# MicroMod_STM32_Processor.net
KiCad netlist of a schematic drawn in EAGLE
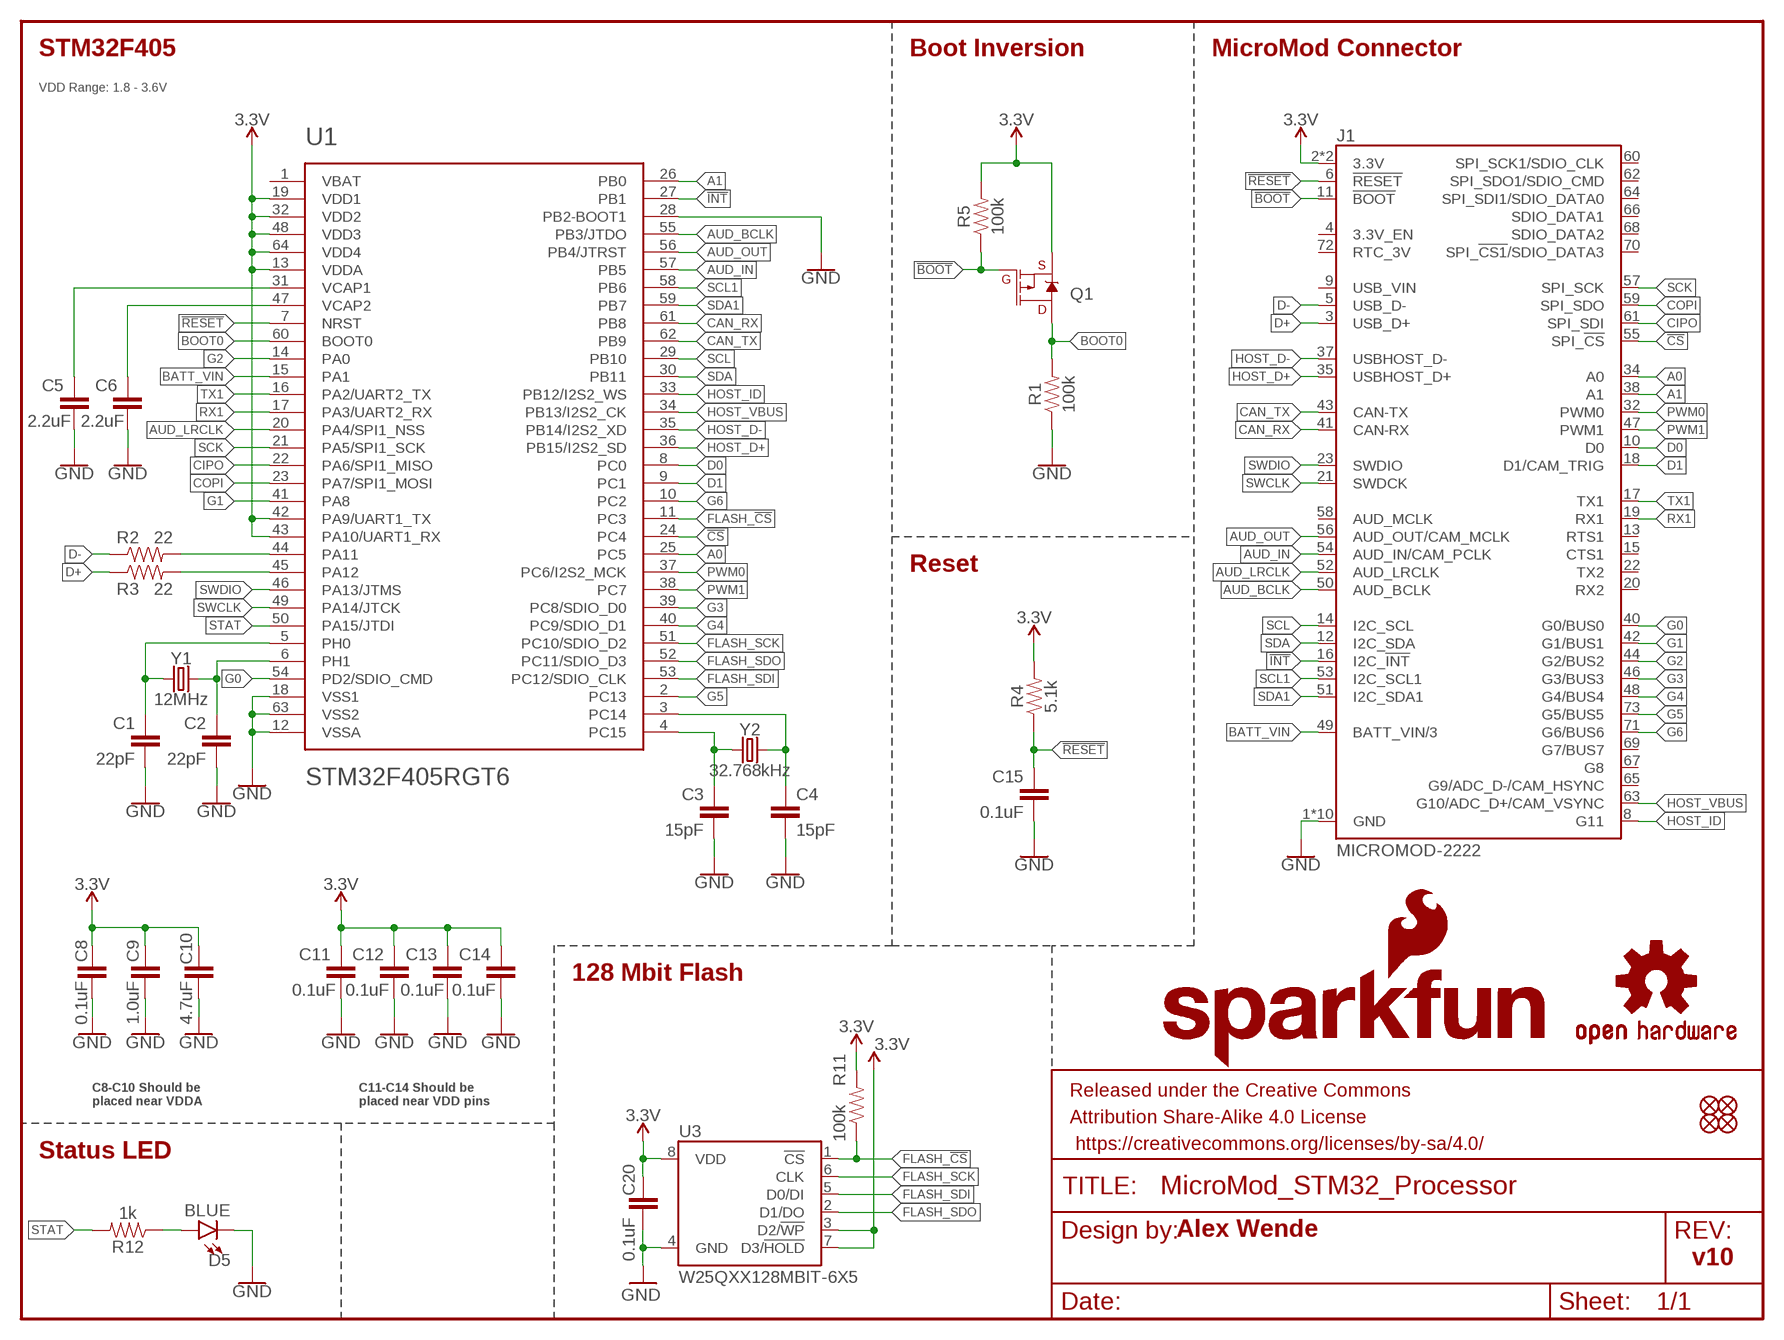
[diagram p0: schematic, sheet 1]

(export (version "E")
  (design (tool "Eeschema 10.0.6"))
  (components
    (comp (ref "C1")
      (value "22pF")
      (footprint "eagle-import:0402-TIGHT")
      (libsource (lib "eagle-import") (part "22PF-0402T-16V-10%"))
    )
    (comp (ref "C2")
      (value "22pF")
      (footprint "eagle-import:0402-TIGHT")
      (libsource (lib "eagle-import") (part "22PF-0402T-16V-10%"))
    )
    (comp (ref "C3")
      (value "15pF")
      (footprint "eagle-import:0402-TIGHT")
      (libsource (lib "eagle-import") (part "15PF-0402T-50V-5%"))
    )
    (comp (ref "C4")
      (value "15pF")
      (footprint "eagle-import:0402-TIGHT")
      (libsource (lib "eagle-import") (part "15PF-0402T-50V-5%"))
    )
    (comp (ref "C5")
      (value "2.2uF")
      (footprint "eagle-import:0402-TIGHT")
      (libsource (lib "eagle-import") (part "2.2UF-0402_TIGHT-10V-10%-X5R"))
    )
    (comp (ref "C6")
      (value "2.2uF")
      (footprint "eagle-import:0402-TIGHT")
      (libsource (lib "eagle-import") (part "2.2UF-0402_TIGHT-10V-10%-X5R"))
    )
    (comp (ref "C8")
      (value "0.1uF")
      (footprint "eagle-import:0402-TIGHT")
      (fields (field (name "SPICEPREFIX") "C"))
      (libsource (lib "eagle-import") (part "0.1UF-0402T-10V-10%-X7R"))
    )
    (comp (ref "C9")
      (value "1.0uF")
      (footprint "eagle-import:0402-TIGHT")
      (fields (field (name "SPICEPREFIX") "C"))
      (libsource (lib "eagle-import") (part "1.0UF-0402T-16V-10%"))
    )
    (comp (ref "C10")
      (value "4.7uF")
      (footprint "eagle-import:0402-TIGHT")
      (fields (field (name "SPICEPREFIX") "C"))
      (libsource (lib "eagle-import") (part "4.7UF-0402_TIGHT-6.3V-20%-X5R"))
    )
    (comp (ref "C11")
      (value "0.1uF")
      (footprint "eagle-import:0402-TIGHT")
      (libsource (lib "eagle-import") (part "0.1UF-0402T-10V-10%-X7R"))
    )
    (comp (ref "C12")
      (value "0.1uF")
      (footprint "eagle-import:0402-TIGHT")
      (libsource (lib "eagle-import") (part "0.1UF-0402T-10V-10%-X7R"))
    )
    (comp (ref "C13")
      (value "0.1uF")
      (footprint "eagle-import:0402-TIGHT")
      (libsource (lib "eagle-import") (part "0.1UF-0402T-10V-10%-X7R"))
    )
    (comp (ref "C14")
      (value "0.1uF")
      (footprint "eagle-import:0402-TIGHT")
      (libsource (lib "eagle-import") (part "0.1UF-0402T-10V-10%-X7R"))
    )
    (comp (ref "C15")
      (value "0.1uF")
      (footprint "eagle-import:0402-TIGHT")
      (libsource (lib "eagle-import") (part "0.1UF-0402T-10V-10%-X7R"))
    )
    (comp (ref "C20")
      (value "0.1uF")
      (footprint "eagle-import:0402-TIGHT")
      (libsource (lib "eagle-import") (part "0.1UF-0402T-10V-10%-X7R"))
    )
    (comp (ref "D5")
      (value "BLUE")
      (footprint "eagle-import:LED-0603")
      (libsource (lib "eagle-import") (part "LED-BLUE0603"))
    )
    (comp (ref "FD1")
      (value "FIDUCIALUFIDUCIAL")
      (footprint "eagle-import:FIDUCIAL-MICRO")
      (libsource (lib "eagle-import") (part "FIDUCIALUFIDUCIAL"))
    )
    (comp (ref "FD2")
      (value "FIDUCIALUFIDUCIAL")
      (footprint "eagle-import:FIDUCIAL-MICRO")
      (libsource (lib "eagle-import") (part "FIDUCIALUFIDUCIAL"))
    )
    (comp (ref "FD3")
      (value "FIDUCIALUFIDUCIAL")
      (footprint "eagle-import:FIDUCIAL-MICRO")
      (libsource (lib "eagle-import") (part "FIDUCIALUFIDUCIAL"))
    )
    (comp (ref "FD4")
      (value "FIDUCIALUFIDUCIAL")
      (footprint "eagle-import:FIDUCIAL-MICRO")
      (libsource (lib "eagle-import") (part "FIDUCIALUFIDUCIAL"))
    )
    (comp (ref "FRAME1")
      (value "FRAME-LETTER")
      (footprint "eagle-import:CREATIVE_COMMONS")
      (libsource (lib "eagle-import") (part "FRAME-LETTER"))
    )
    (comp (ref "J1")
      (value "MICROMOD-2222")
      (footprint "eagle-import:M.2-CARD-E-22")
      (libsource (lib "eagle-import") (part "MICROMOD-2222"))
    )
    (comp (ref "LOGO2")
      (value "OSHW-LOGOS")
      (footprint "eagle-import:OSHW-LOGO-S")
      (libsource (lib "eagle-import") (part "OSHW-LOGOS"))
    )
    (comp (ref "LOGO3")
      (value "SFE_LOGO_NAME_FLAME.1_INCH")
      (footprint "eagle-import:SFE_LOGO_NAME_FLAME_.1")
      (libsource (lib "eagle-import") (part "SFE_LOGO_NAME_FLAME.1_INCH"))
    )
    (comp (ref "Q1")
      (value "MOSFET_PCH-DMG2305UX-7")
      (footprint "eagle-import:SOT23-3")
      (libsource (lib "eagle-import") (part "MOSFET_PCH-DMG2305UX-7"))
    )
    (comp (ref "R1")
      (value "100k")
      (footprint "eagle-import:0402-TIGHT")
      (libsource (lib "eagle-import") (part "100KOHM-0402T-1/16W-1%"))
    )
    (comp (ref "R2")
      (value "22")
      (footprint "eagle-import:0402-TIGHT")
      (libsource (lib "eagle-import") (part "22OHM-0402T-1/16W-1%"))
    )
    (comp (ref "R3")
      (value "22")
      (footprint "eagle-import:0402-TIGHT")
      (libsource (lib "eagle-import") (part "22OHM-0402T-1/16W-1%"))
    )
    (comp (ref "R4")
      (value "5.1k")
      (footprint "eagle-import:0402-TIGHT")
      (libsource (lib "eagle-import") (part "5.1KOHM-0402T-1/16W-1%"))
    )
    (comp (ref "R5")
      (value "100k")
      (footprint "eagle-import:0402-TIGHT")
      (libsource (lib "eagle-import") (part "100KOHM-0402T-1/16W-1%"))
    )
    (comp (ref "R11")
      (value "100k")
      (footprint "eagle-import:0402-TIGHT")
      (libsource (lib "eagle-import") (part "100KOHM-0402T-1/16W-1%"))
    )
    (comp (ref "R12")
      (value "1k")
      (footprint "eagle-import:0402-TIGHT")
      (libsource (lib "eagle-import") (part "1KOHM-0402T-1/16W-1%"))
    )
    (comp (ref "U1")
      (value "STM32F405RGT6")
      (footprint "eagle-import:TQFP64")
      (libsource (lib "eagle-import") (part "STM32F405RG"))
    )
    (comp (ref "U3")
      (value "W25QXX128MBIT-6X5")
      (footprint "eagle-import:WSON-8-6X5")
      (libsource (lib "eagle-import") (part "W25QXX128MBIT-6X5"))
    )
    (comp (ref "Y1")
      (value "12MHz")
      (footprint "eagle-import:CRYSTAL-SMD-5X3.2-4PAD")
      (libsource (lib "eagle-import") (part "CRYSTAL-12MHZ{dblquote}"))
    )
    (comp (ref "Y2")
      (value "32.768kHz")
      (footprint "eagle-import:CRYSTAL-SMD-3.2X1.5MM")
      (libsource (lib "eagle-import") (part "CRYSTAL-32.768KHZSMD-3.2X1.5"))
    )
  )
  (nets
    (net (code "1") (name "/FLASH_~{CS}") (class "Default")
      (node (ref "R11") (pin "1") (pinfunction "1_1") (pintype "passive"))
      (node (ref "U1") (pin "11") (pinfunction "PC3_11") (pintype "bidirectional"))
      (node (ref "U3") (pin "1") (pinfunction "~{CS}_1") (pintype "bidirectional"))
    )
    (net (code "2") (name "/~{BOOT}") (class "Default")
      (node (ref "J1") (pin "11") (pinfunction "~{BOOT}_11") (pintype "bidirectional"))
      (node (ref "Q1") (pin "1") (pinfunction "G_1") (pintype "bidirectional"))
      (node (ref "R5") (pin "1") (pinfunction "1_1") (pintype "passive"))
    )
    (net (code "3") (name "/~{CS}") (class "Default")
      (node (ref "J1") (pin "55") (pinfunction "SPI_~{CS}_55") (pintype "bidirectional"))
      (node (ref "U1") (pin "24") (pinfunction "PC4_24") (pintype "bidirectional"))
    )
    (net (code "4") (name "/~{INT}") (class "Default")
      (node (ref "J1") (pin "16") (pinfunction "I2C_~{INT}_16") (pintype "bidirectional"))
      (node (ref "U1") (pin "27") (pinfunction "PB1_27") (pintype "bidirectional"))
    )
    (net (code "5") (name "/~{RESET}") (class "Default")
      (node (ref "C15") (pin "1") (pinfunction "1_1") (pintype "passive"))
      (node (ref "J1") (pin "6") (pinfunction "~{RESET}_6") (pintype "bidirectional"))
      (node (ref "R4") (pin "1") (pinfunction "1_1") (pintype "passive"))
      (node (ref "U1") (pin "7") (pinfunction "NRST_7") (pintype "bidirectional"))
    )
    (net (code "6") (name "3.3V") (class "Default")
      (node (ref "C10") (pin "1") (pinfunction "1_1") (pintype "passive"))
      (node (ref "C11") (pin "1") (pinfunction "1_1") (pintype "passive"))
      (node (ref "C12") (pin "1") (pinfunction "1_1") (pintype "passive"))
      (node (ref "C13") (pin "1") (pinfunction "1_1") (pintype "passive"))
      (node (ref "C14") (pin "1") (pinfunction "1_1") (pintype "passive"))
      (node (ref "C20") (pin "1") (pinfunction "1_1") (pintype "passive"))
      (node (ref "C8") (pin "1") (pinfunction "1_1") (pintype "passive"))
      (node (ref "C9") (pin "1") (pinfunction "1_1") (pintype "passive"))
      (node (ref "J1") (pin "2") (pinfunction "3.3V_2") (pintype "bidirectional"))
      (node (ref "J1") (pin "74") (pinfunction "3.3V_74") (pintype "bidirectional"))
      (node (ref "Q1") (pin "2") (pinfunction "S_2") (pintype "bidirectional"))
      (node (ref "R11") (pin "2") (pinfunction "2_2") (pintype "passive"))
      (node (ref "R4") (pin "2") (pinfunction "2_2") (pintype "passive"))
      (node (ref "R5") (pin "2") (pinfunction "2_2") (pintype "passive"))
      (node (ref "U1") (pin "13") (pinfunction "VDDA_13") (pintype "bidirectional"))
      (node (ref "U1") (pin "19") (pinfunction "VDD1_19") (pintype "bidirectional"))
      (node (ref "U1") (pin "32") (pinfunction "VDD2_32") (pintype "bidirectional"))
      (node (ref "U1") (pin "42") (pinfunction "PA9/UART1_TX_42") (pintype "bidirectional"))
      (node (ref "U1") (pin "43") (pinfunction "PA10/UART1_RX_43") (pintype "bidirectional"))
      (node (ref "U1") (pin "48") (pinfunction "VDD3_48") (pintype "bidirectional"))
      (node (ref "U1") (pin "64") (pinfunction "VDD4_64") (pintype "bidirectional"))
      (node (ref "U3") (pin "3") (pinfunction "D2/~{WP}_3") (pintype "bidirectional"))
      (node (ref "U3") (pin "7") (pinfunction "D3/~{HOLD}_7") (pintype "bidirectional"))
      (node (ref "U3") (pin "8") (pinfunction "VDD_8") (pintype "bidirectional"))
    )
    (net (code "7") (name "A0") (class "Default")
      (node (ref "J1") (pin "34") (pinfunction "A0_34") (pintype "bidirectional"))
      (node (ref "U1") (pin "25") (pinfunction "PC5_25") (pintype "bidirectional"))
    )
    (net (code "8") (name "A1") (class "Default")
      (node (ref "J1") (pin "38") (pinfunction "A1_38") (pintype "bidirectional"))
      (node (ref "U1") (pin "26") (pinfunction "PB0_26") (pintype "bidirectional"))
    )
    (net (code "9") (name "AUD_BCLK") (class "Default")
      (node (ref "J1") (pin "50") (pinfunction "AUD_BCLK_50") (pintype "bidirectional"))
      (node (ref "U1") (pin "55") (pinfunction "PB3/JTDO_55") (pintype "bidirectional"))
    )
    (net (code "10") (name "AUD_IN") (class "Default")
      (node (ref "J1") (pin "54") (pinfunction "AUD_IN/CAM_PCLK_54") (pintype "bidirectional"))
      (node (ref "U1") (pin "57") (pinfunction "PB5_57") (pintype "bidirectional"))
    )
    (net (code "11") (name "AUD_LRCLK") (class "Default")
      (node (ref "J1") (pin "52") (pinfunction "AUD_LRCLK_52") (pintype "bidirectional"))
      (node (ref "U1") (pin "20") (pinfunction "PA4/SPI1_NSS_20") (pintype "bidirectional"))
    )
    (net (code "12") (name "AUD_OUT") (class "Default")
      (node (ref "J1") (pin "56") (pinfunction "AUD_OUT/CAM_MCLK_56") (pintype "bidirectional"))
      (node (ref "U1") (pin "56") (pinfunction "PB4/JTRST_56") (pintype "bidirectional"))
    )
    (net (code "13") (name "BATT_VIN") (class "Default")
      (node (ref "J1") (pin "49") (pinfunction "BATT_VIN/3_49") (pintype "bidirectional"))
      (node (ref "U1") (pin "15") (pinfunction "PA1_15") (pintype "bidirectional"))
    )
    (net (code "14") (name "BOOT0") (class "Default")
      (node (ref "Q1") (pin "3") (pinfunction "D_3") (pintype "bidirectional"))
      (node (ref "R1") (pin "2") (pinfunction "2_2") (pintype "passive"))
      (node (ref "U1") (pin "60") (pinfunction "BOOT0_60") (pintype "bidirectional"))
    )
    (net (code "15") (name "CAN_RX") (class "Default")
      (node (ref "J1") (pin "41") (pinfunction "CAN-RX_41") (pintype "bidirectional"))
      (node (ref "U1") (pin "61") (pinfunction "PB8_61") (pintype "bidirectional"))
    )
    (net (code "16") (name "CAN_TX") (class "Default")
      (node (ref "J1") (pin "43") (pinfunction "CAN-TX_43") (pintype "bidirectional"))
      (node (ref "U1") (pin "62") (pinfunction "PB9_62") (pintype "bidirectional"))
    )
    (net (code "17") (name "CIPO") (class "Default")
      (node (ref "J1") (pin "61") (pinfunction "SPI_SDI_61") (pintype "bidirectional"))
      (node (ref "U1") (pin "22") (pinfunction "PA6/SPI1_MISO_22") (pintype "bidirectional"))
    )
    (net (code "18") (name "COPI") (class "Default")
      (node (ref "J1") (pin "59") (pinfunction "SPI_SDO_59") (pintype "bidirectional"))
      (node (ref "U1") (pin "23") (pinfunction "PA7/SPI1_MOSI_23") (pintype "bidirectional"))
    )
    (net (code "19") (name "D+") (class "Default")
      (node (ref "J1") (pin "3") (pinfunction "USB_D+_3") (pintype "bidirectional"))
      (node (ref "R3") (pin "1") (pinfunction "1_1") (pintype "passive"))
    )
    (net (code "20") (name "D-") (class "Default")
      (node (ref "J1") (pin "5") (pinfunction "USB_D-_5") (pintype "bidirectional"))
      (node (ref "R2") (pin "1") (pinfunction "1_1") (pintype "passive"))
    )
    (net (code "21") (name "D0") (class "Default")
      (node (ref "J1") (pin "10") (pinfunction "D0_10") (pintype "bidirectional"))
      (node (ref "U1") (pin "8") (pinfunction "PC0_8") (pintype "bidirectional"))
    )
    (net (code "22") (name "D1") (class "Default")
      (node (ref "J1") (pin "18") (pinfunction "D1/CAM_TRIG_18") (pintype "bidirectional"))
      (node (ref "U1") (pin "9") (pinfunction "PC1_9") (pintype "bidirectional"))
    )
    (net (code "23") (name "FLASH_SCK") (class "Default")
      (node (ref "U1") (pin "51") (pinfunction "PC10/SDIO_D2_51") (pintype "bidirectional"))
      (node (ref "U3") (pin "6") (pinfunction "CLK_6") (pintype "bidirectional"))
    )
    (net (code "24") (name "FLASH_SDI") (class "Default")
      (node (ref "U1") (pin "53") (pinfunction "PC12/SDIO_CLK_53") (pintype "bidirectional"))
      (node (ref "U3") (pin "5") (pinfunction "D0/DI_5") (pintype "bidirectional"))
    )
    (net (code "25") (name "FLASH_SDO") (class "Default")
      (node (ref "U1") (pin "52") (pinfunction "PC11/SDIO_D3_52") (pintype "bidirectional"))
      (node (ref "U3") (pin "2") (pinfunction "D1/DO_2") (pintype "bidirectional"))
    )
    (net (code "26") (name "G0") (class "Default")
      (node (ref "J1") (pin "40") (pinfunction "G0/BUS0_40") (pintype "bidirectional"))
      (node (ref "U1") (pin "54") (pinfunction "PD2/SDIO_CMD_54") (pintype "bidirectional"))
    )
    (net (code "27") (name "G1") (class "Default")
      (node (ref "J1") (pin "42") (pinfunction "G1/BUS1_42") (pintype "bidirectional"))
      (node (ref "U1") (pin "41") (pinfunction "PA8_41") (pintype "bidirectional"))
    )
    (net (code "28") (name "G2") (class "Default")
      (node (ref "J1") (pin "44") (pinfunction "G2/BUS2_44") (pintype "bidirectional"))
      (node (ref "U1") (pin "14") (pinfunction "PA0_14") (pintype "bidirectional"))
    )
    (net (code "29") (name "G3") (class "Default")
      (node (ref "J1") (pin "46") (pinfunction "G3/BUS3_46") (pintype "bidirectional"))
      (node (ref "U1") (pin "39") (pinfunction "PC8/SDIO_D0_39") (pintype "bidirectional"))
    )
    (net (code "30") (name "G4") (class "Default")
      (node (ref "J1") (pin "48") (pinfunction "G4/BUS4_48") (pintype "bidirectional"))
      (node (ref "U1") (pin "40") (pinfunction "PC9/SDIO_D1_40") (pintype "bidirectional"))
    )
    (net (code "31") (name "G5") (class "Default")
      (node (ref "J1") (pin "73") (pinfunction "G5/BUS5_73") (pintype "bidirectional"))
      (node (ref "U1") (pin "2") (pinfunction "PC13_2") (pintype "bidirectional"))
    )
    (net (code "32") (name "G6") (class "Default")
      (node (ref "J1") (pin "71") (pinfunction "G6/BUS6_71") (pintype "bidirectional"))
      (node (ref "U1") (pin "10") (pinfunction "PC2_10") (pintype "bidirectional"))
    )
    (net (code "33") (name "GND") (class "Default")
      (node (ref "C1") (pin "2") (pinfunction "2_2") (pintype "passive"))
      (node (ref "C10") (pin "2") (pinfunction "2_2") (pintype "passive"))
      (node (ref "C11") (pin "2") (pinfunction "2_2") (pintype "passive"))
      (node (ref "C12") (pin "2") (pinfunction "2_2") (pintype "passive"))
      (node (ref "C13") (pin "2") (pinfunction "2_2") (pintype "passive"))
      (node (ref "C14") (pin "2") (pinfunction "2_2") (pintype "passive"))
      (node (ref "C15") (pin "2") (pinfunction "2_2") (pintype "passive"))
      (node (ref "C2") (pin "2") (pinfunction "2_2") (pintype "passive"))
      (node (ref "C20") (pin "2") (pinfunction "2_2") (pintype "passive"))
      (node (ref "C3") (pin "2") (pinfunction "2_2") (pintype "passive"))
      (node (ref "C4") (pin "2") (pinfunction "2_2") (pintype "passive"))
      (node (ref "C5") (pin "2") (pinfunction "2_2") (pintype "passive"))
      (node (ref "C6") (pin "2") (pinfunction "2_2") (pintype "passive"))
      (node (ref "C8") (pin "2") (pinfunction "2_2") (pintype "passive"))
      (node (ref "C9") (pin "2") (pinfunction "2_2") (pintype "passive"))
      (node (ref "D5") (pin "C") (pinfunction "C_C") (pintype "passive"))
      (node (ref "J1") (pin "1") (pinfunction "GND_1") (pintype "bidirectional"))
      (node (ref "J1") (pin "33") (pinfunction "GND_33") (pintype "bidirectional"))
      (node (ref "J1") (pin "36") (pinfunction "GND_36") (pintype "bidirectional"))
      (node (ref "J1") (pin "39") (pinfunction "GND_39") (pintype "bidirectional"))
      (node (ref "J1") (pin "45") (pinfunction "GND_45") (pintype "bidirectional"))
      (node (ref "J1") (pin "7") (pinfunction "GND_7") (pintype "bidirectional"))
      (node (ref "J1") (pin "75") (pinfunction "GND_75") (pintype "bidirectional"))
      (node (ref "J1") (pin "GND1") (pinfunction "GND_GND1") (pintype "bidirectional"))
      (node (ref "J1") (pin "GND2") (pinfunction "GND_GND2") (pintype "bidirectional"))
      (node (ref "J1") (pin "GND3") (pinfunction "GND_GND3") (pintype "bidirectional"))
      (node (ref "R1") (pin "1") (pinfunction "1_1") (pintype "passive"))
      (node (ref "U1") (pin "12") (pinfunction "VSSA_12") (pintype "bidirectional"))
      (node (ref "U1") (pin "18") (pinfunction "VSS1_18") (pintype "bidirectional"))
      (node (ref "U1") (pin "28") (pinfunction "PB2-BOOT1_28") (pintype "bidirectional"))
      (node (ref "U1") (pin "63") (pinfunction "VSS2_63") (pintype "bidirectional"))
      (node (ref "U3") (pin "4") (pinfunction "GND_4") (pintype "bidirectional"))
    )
    (net (code "34") (name "HOST_D+") (class "Default")
      (node (ref "J1") (pin "35") (pinfunction "USBHOST_D+_35") (pintype "bidirectional"))
      (node (ref "U1") (pin "36") (pinfunction "PB15/I2S2_SD_36") (pintype "bidirectional"))
    )
    (net (code "35") (name "HOST_D-") (class "Default")
      (node (ref "J1") (pin "37") (pinfunction "USBHOST_D-_37") (pintype "bidirectional"))
      (node (ref "U1") (pin "35") (pinfunction "PB14/I2S2_XD_35") (pintype "bidirectional"))
    )
    (net (code "36") (name "HOST_ID") (class "Default")
      (node (ref "J1") (pin "8") (pinfunction "G11_8") (pintype "bidirectional"))
      (node (ref "U1") (pin "33") (pinfunction "PB12/I2S2_WS_33") (pintype "bidirectional"))
    )
    (net (code "37") (name "HOST_VBUS") (class "Default")
      (node (ref "J1") (pin "63") (pinfunction "G10/ADC_D+/CAM_VSYNC_63") (pintype "bidirectional"))
      (node (ref "U1") (pin "34") (pinfunction "PB13/I2S2_CK_34") (pintype "bidirectional"))
    )
    (net (code "38") (name "Net-(D5-PadA)") (class "Default")
      (node (ref "D5") (pin "A") (pinfunction "A_A") (pintype "passive"))
      (node (ref "R12") (pin "1") (pinfunction "1_1") (pintype "passive"))
    )
    (net (code "39") (name "Net-(U1-PA11)") (class "Default")
      (node (ref "R2") (pin "2") (pinfunction "2_2") (pintype "passive"))
      (node (ref "U1") (pin "44") (pinfunction "PA11_44") (pintype "bidirectional"))
    )
    (net (code "40") (name "Net-(U1-PA12)") (class "Default")
      (node (ref "R3") (pin "2") (pinfunction "2_2") (pintype "passive"))
      (node (ref "U1") (pin "45") (pinfunction "PA12_45") (pintype "bidirectional"))
    )
    (net (code "41") (name "Net-(U1-PC14)") (class "Default")
      (node (ref "C4") (pin "1") (pinfunction "1_1") (pintype "passive"))
      (node (ref "U1") (pin "3") (pinfunction "PC14_3") (pintype "bidirectional"))
      (node (ref "Y2") (pin "P$2") (pinfunction "2_P$2") (pintype "passive"))
    )
    (net (code "42") (name "Net-(U1-PC15)") (class "Default")
      (node (ref "C3") (pin "1") (pinfunction "1_1") (pintype "passive"))
      (node (ref "U1") (pin "4") (pinfunction "PC15_4") (pintype "bidirectional"))
      (node (ref "Y2") (pin "P$1") (pinfunction "1_P$1") (pintype "passive"))
    )
    (net (code "43") (name "Net-(U1-PH0)") (class "Default")
      (node (ref "C1") (pin "1") (pinfunction "1_1") (pintype "passive"))
      (node (ref "U1") (pin "5") (pinfunction "PH0_5") (pintype "bidirectional"))
      (node (ref "Y1") (pin "1") (pinfunction "1_1") (pintype "passive"))
    )
    (net (code "44") (name "Net-(U1-PH1)") (class "Default")
      (node (ref "C2") (pin "1") (pinfunction "1_1") (pintype "passive"))
      (node (ref "U1") (pin "6") (pinfunction "PH1_6") (pintype "bidirectional"))
      (node (ref "Y1") (pin "3") (pinfunction "2_3") (pintype "passive"))
    )
    (net (code "45") (name "Net-(U1-VCAP1)") (class "Default")
      (node (ref "C5") (pin "1") (pinfunction "1_1") (pintype "passive"))
      (node (ref "U1") (pin "31") (pinfunction "VCAP1_31") (pintype "bidirectional"))
    )
    (net (code "46") (name "Net-(U1-VCAP2)") (class "Default")
      (node (ref "C6") (pin "1") (pinfunction "1_1") (pintype "passive"))
      (node (ref "U1") (pin "47") (pinfunction "VCAP2_47") (pintype "bidirectional"))
    )
    (net (code "47") (name "PWM0") (class "Default")
      (node (ref "J1") (pin "32") (pinfunction "PWM0_32") (pintype "bidirectional"))
      (node (ref "U1") (pin "37") (pinfunction "PC6/I2S2_MCK_37") (pintype "bidirectional"))
    )
    (net (code "48") (name "PWM1") (class "Default")
      (node (ref "J1") (pin "47") (pinfunction "PWM1_47") (pintype "bidirectional"))
      (node (ref "U1") (pin "38") (pinfunction "PC7_38") (pintype "bidirectional"))
    )
    (net (code "49") (name "RX1") (class "Default")
      (node (ref "J1") (pin "19") (pinfunction "RX1_19") (pintype "bidirectional"))
      (node (ref "U1") (pin "17") (pinfunction "PA3/UART2_RX_17") (pintype "bidirectional"))
    )
    (net (code "50") (name "SCK") (class "Default")
      (node (ref "J1") (pin "57") (pinfunction "SPI_SCK_57") (pintype "bidirectional"))
      (node (ref "U1") (pin "21") (pinfunction "PA5/SPI1_SCK_21") (pintype "bidirectional"))
    )
    (net (code "51") (name "SCL") (class "Default")
      (node (ref "J1") (pin "14") (pinfunction "I2C_SCL_14") (pintype "bidirectional"))
      (node (ref "U1") (pin "29") (pinfunction "PB10_29") (pintype "bidirectional"))
    )
    (net (code "52") (name "SCL1") (class "Default")
      (node (ref "J1") (pin "53") (pinfunction "I2C_SCL1_53") (pintype "bidirectional"))
      (node (ref "U1") (pin "58") (pinfunction "PB6_58") (pintype "bidirectional"))
    )
    (net (code "53") (name "SDA") (class "Default")
      (node (ref "J1") (pin "12") (pinfunction "I2C_SDA_12") (pintype "bidirectional"))
      (node (ref "U1") (pin "30") (pinfunction "PB11_30") (pintype "bidirectional"))
    )
    (net (code "54") (name "SDA1") (class "Default")
      (node (ref "J1") (pin "51") (pinfunction "I2C_SDA1_51") (pintype "bidirectional"))
      (node (ref "U1") (pin "59") (pinfunction "PB7_59") (pintype "bidirectional"))
    )
    (net (code "55") (name "STAT") (class "Default")
      (node (ref "R12") (pin "2") (pinfunction "2_2") (pintype "passive"))
      (node (ref "U1") (pin "50") (pinfunction "PA15/JTDI_50") (pintype "bidirectional"))
    )
    (net (code "56") (name "SWCLK") (class "Default")
      (node (ref "J1") (pin "21") (pinfunction "SWDCK_21") (pintype "bidirectional"))
      (node (ref "U1") (pin "49") (pinfunction "PA14/JTCK_49") (pintype "bidirectional"))
    )
    (net (code "57") (name "SWDIO") (class "Default")
      (node (ref "J1") (pin "23") (pinfunction "SWDIO_23") (pintype "bidirectional"))
      (node (ref "U1") (pin "46") (pinfunction "PA13/JTMS_46") (pintype "bidirectional"))
    )
    (net (code "58") (name "TX1") (class "Default")
      (node (ref "J1") (pin "17") (pinfunction "TX1_17") (pintype "bidirectional"))
      (node (ref "U1") (pin "16") (pinfunction "PA2/UART2_TX_16") (pintype "bidirectional"))
    )
    (net (code "59") (name "unconnected-(J1-3.3V_EN-Pad4)") (class "Default")
      (node (ref "J1") (pin "4") (pinfunction "3.3V_EN_4") (pintype "bidirectional"))
    )
    (net (code "60") (name "unconnected-(J1-AUD_MCLK-Pad58)") (class "Default")
      (node (ref "J1") (pin "58") (pinfunction "AUD_MCLK_58") (pintype "bidirectional"))
    )
    (net (code "61") (name "unconnected-(J1-CTS1-Pad15)") (class "Default")
      (node (ref "J1") (pin "15") (pinfunction "CTS1_15") (pintype "bidirectional"))
    )
    (net (code "62") (name "unconnected-(J1-G7{slash}BUS7-Pad69)") (class "Default")
      (node (ref "J1") (pin "69") (pinfunction "G7/BUS7_69") (pintype "bidirectional"))
    )
    (net (code "63") (name "unconnected-(J1-G8-Pad67)") (class "Default")
      (node (ref "J1") (pin "67") (pinfunction "G8_67") (pintype "bidirectional"))
    )
    (net (code "64") (name "unconnected-(J1-G9{slash}ADC_D-{slash}CAM_HSYNC-Pad65)") (class "Default")
      (node (ref "J1") (pin "65") (pinfunction "G9/ADC_D-/CAM_HSYNC_65") (pintype "bidirectional"))
    )
    (net (code "65") (name "unconnected-(J1-RTC_3V-Pad72)") (class "Default")
      (node (ref "J1") (pin "72") (pinfunction "RTC_3V_72") (pintype "bidirectional"))
    )
    (net (code "66") (name "unconnected-(J1-RTS1-Pad13)") (class "Default")
      (node (ref "J1") (pin "13") (pinfunction "RTS1_13") (pintype "bidirectional"))
    )
    (net (code "67") (name "unconnected-(J1-RX2-Pad20)") (class "Default")
      (node (ref "J1") (pin "20") (pinfunction "RX2_20") (pintype "bidirectional"))
    )
    (net (code "68") (name "unconnected-(J1-SDIO_DATA1-Pad66)") (class "Default")
      (node (ref "J1") (pin "66") (pinfunction "SDIO_DATA1_66") (pintype "bidirectional"))
    )
    (net (code "69") (name "unconnected-(J1-SDIO_DATA2-Pad68)") (class "Default")
      (node (ref "J1") (pin "68") (pinfunction "SDIO_DATA2_68") (pintype "bidirectional"))
    )
    (net (code "70") (name "unconnected-(J1-SPI_SCK1{slash}SDIO_CLK-Pad60)") (class "Default")
      (node (ref "J1") (pin "60") (pinfunction "SPI_SCK1/SDIO_CLK_60") (pintype "bidirectional"))
    )
    (net (code "71") (name "unconnected-(J1-SPI_SDI1{slash}SDIO_DATA0-Pad64)") (class "Default")
      (node (ref "J1") (pin "64") (pinfunction "SPI_SDI1/SDIO_DATA0_64") (pintype "bidirectional"))
    )
    (net (code "72") (name "unconnected-(J1-SPI_SDO1{slash}SDIO_CMD-Pad62)") (class "Default")
      (node (ref "J1") (pin "62") (pinfunction "SPI_SDO1/SDIO_CMD_62") (pintype "bidirectional"))
    )
    (net (code "73") (name "unconnected-(J1-SPI_~{CS1}{slash}SDIO_DATA3-Pad70)") (class "Default")
      (node (ref "J1") (pin "70") (pinfunction "SPI_~{CS1}/SDIO_DATA3_70") (pintype "bidirectional"))
    )
    (net (code "74") (name "unconnected-(J1-TX2-Pad22)") (class "Default")
      (node (ref "J1") (pin "22") (pinfunction "TX2_22") (pintype "bidirectional"))
    )
    (net (code "75") (name "unconnected-(J1-USB_VIN-Pad9)") (class "Default")
      (node (ref "J1") (pin "9") (pinfunction "USB_VIN_9") (pintype "bidirectional"))
    )
    (net (code "76") (name "unconnected-(U1-VBAT-Pad1)") (class "Default")
      (node (ref "U1") (pin "1") (pinfunction "VBAT_1") (pintype "bidirectional"))
    )
  )
)
